# Controller_PCB_v1.net
KiCad netlist of a schematic drawn in EAGLE
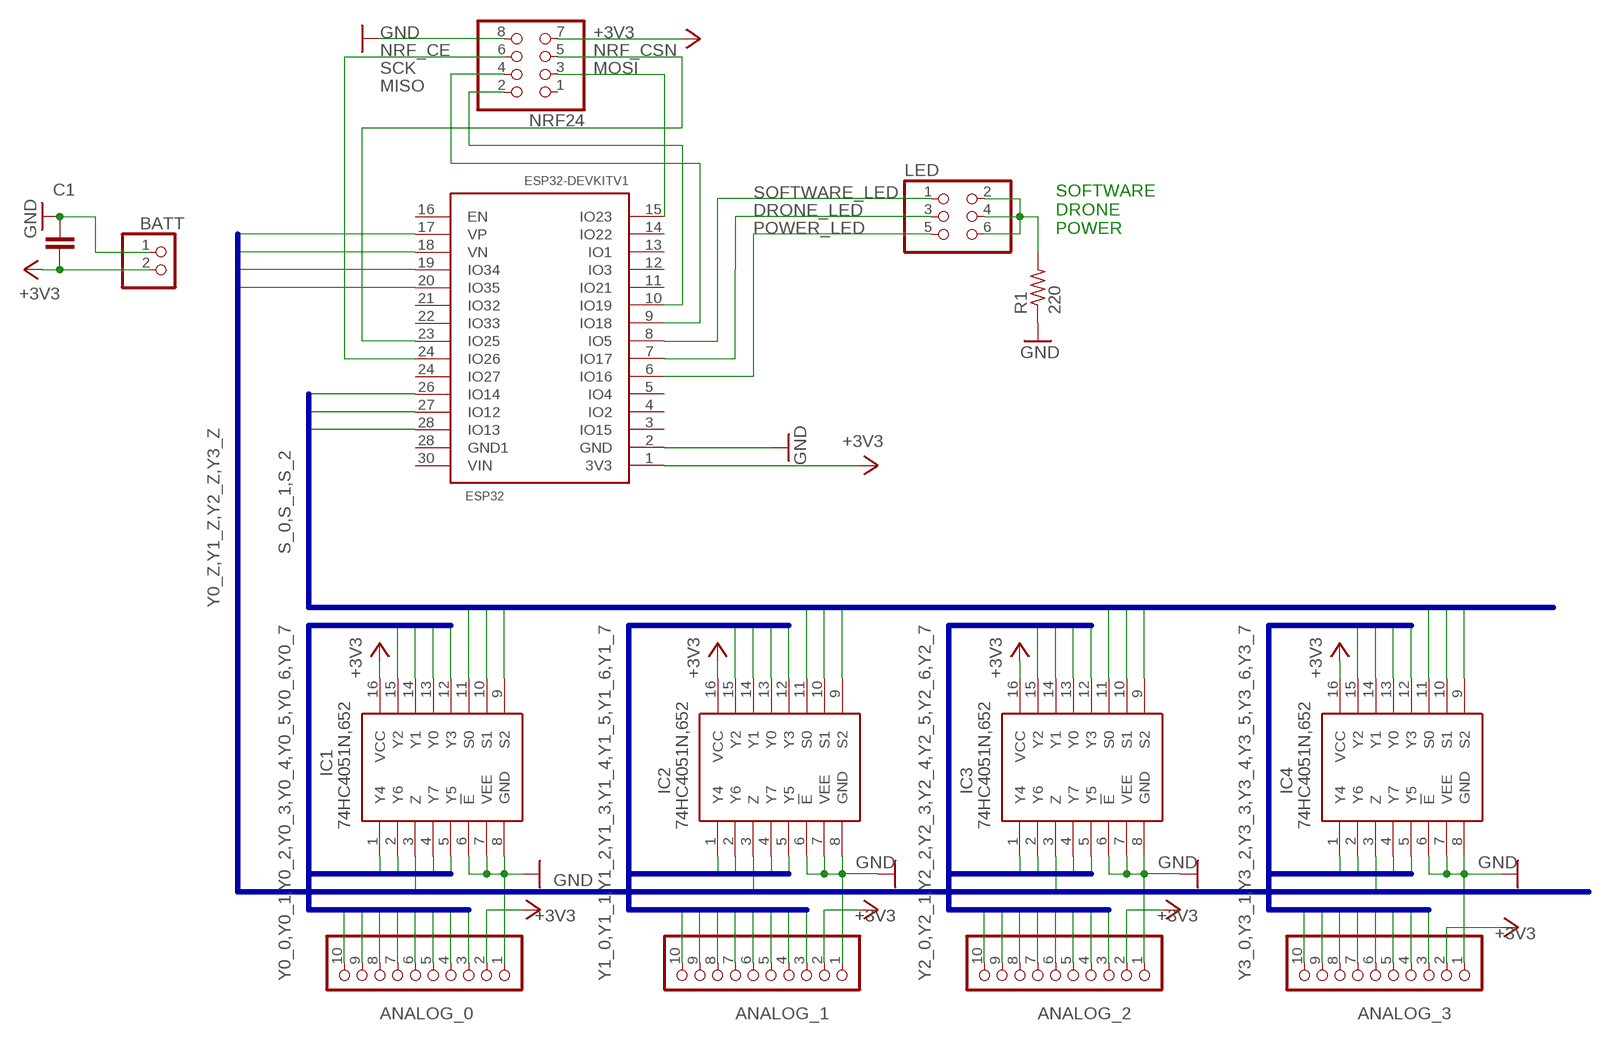
[diagram p0: schematic, sheet 1]

(export (version "E")
  (design (tool "Eeschema 10.0.6"))
  (components
    (comp (ref "ANALOG_0")
      (value "PINHD-1X10/90")
      (footprint "eagle-import:1X10_90")
      (libsource (lib "eagle-import") (part "PINHD-1X10/90"))
    )
    (comp (ref "ANALOG_1")
      (value "PINHD-1X10/90")
      (footprint "eagle-import:1X10_90")
      (libsource (lib "eagle-import") (part "PINHD-1X10/90"))
    )
    (comp (ref "ANALOG_2")
      (value "PINHD-1X10/90")
      (footprint "eagle-import:1X10_90")
      (libsource (lib "eagle-import") (part "PINHD-1X10/90"))
    )
    (comp (ref "ANALOG_3")
      (value "PINHD-1X10/90")
      (footprint "eagle-import:1X10_90")
      (libsource (lib "eagle-import") (part "PINHD-1X10/90"))
    )
    (comp (ref "BATT")
      (value "PINHD-1X2")
      (footprint "eagle-import:1X02")
      (libsource (lib "eagle-import") (part "PINHD-1X2"))
    )
    (comp (ref "C1")
      (value "C2.5/2")
      (footprint "eagle-import:C2.5-2")
      (libsource (lib "eagle-import") (part "C2.5/2"))
    )
    (comp (ref "ESP32")
      (value "ESP32DEVKITV1")
      (footprint "eagle-import:ESP32-DEVKITV1")
      (libsource (lib "eagle-import") (part "ESP32DEVKITV1"))
    )
    (comp (ref "IC1")
      (value "74HC4051N,652")
      (footprint "eagle-import:DIP802W53P254L1902H420Q16N")
      (libsource (lib "eagle-import") (part "74HC4051N,652"))
    )
    (comp (ref "IC2")
      (value "74HC4051N,652")
      (footprint "eagle-import:DIP802W53P254L1902H420Q16N")
      (libsource (lib "eagle-import") (part "74HC4051N,652"))
    )
    (comp (ref "IC3")
      (value "74HC4051N,652")
      (footprint "eagle-import:DIP802W53P254L1902H420Q16N")
      (libsource (lib "eagle-import") (part "74HC4051N,652"))
    )
    (comp (ref "IC4")
      (value "74HC4051N,652")
      (footprint "eagle-import:DIP802W53P254L1902H420Q16N")
      (libsource (lib "eagle-import") (part "74HC4051N,652"))
    )
    (comp (ref "LED")
      (value "PINHD-2X3")
      (footprint "eagle-import:2X03")
      (libsource (lib "eagle-import") (part "PINHD-2X3"))
    )
    (comp (ref "NRF24")
      (value "PINHD-2X4/90")
      (footprint "eagle-import:2X04_90")
      (libsource (lib "eagle-import") (part "PINHD-2X4/90"))
    )
    (comp (ref "R1")
      (value "220")
      (footprint "eagle-import:0204_7")
      (libsource (lib "eagle-import") (part "R-US_0204/7"))
    )
  )
  (nets
    (net (code "1") (name "+3V3") (class "Default")
      (node (ref "ANALOG_0") (pin "2") (pinfunction "2_2") (pintype "passive"))
      (node (ref "ANALOG_1") (pin "2") (pinfunction "2_2") (pintype "passive"))
      (node (ref "ANALOG_2") (pin "2") (pinfunction "2_2") (pintype "passive"))
      (node (ref "ANALOG_3") (pin "2") (pinfunction "2_2") (pintype "passive"))
      (node (ref "BATT") (pin "2") (pinfunction "2_2") (pintype "passive"))
      (node (ref "C1") (pin "2") (pinfunction "2_2") (pintype "passive"))
      (node (ref "ESP32") (pin "1") (pinfunction "3V3_1") (pintype "bidirectional"))
      (node (ref "IC1") (pin "16") (pinfunction "VCC_16") (pintype "bidirectional"))
      (node (ref "IC2") (pin "16") (pinfunction "VCC_16") (pintype "bidirectional"))
      (node (ref "IC3") (pin "16") (pinfunction "VCC_16") (pintype "bidirectional"))
      (node (ref "IC4") (pin "16") (pinfunction "VCC_16") (pintype "bidirectional"))
      (node (ref "NRF24") (pin "7") (pinfunction "7_7") (pintype "passive"))
    )
    (net (code "2") (name "/DRONE_LED") (class "Default")
      (node (ref "ESP32") (pin "7") (pinfunction "IO17_7") (pintype "bidirectional"))
      (node (ref "LED") (pin "3") (pinfunction "3_3") (pintype "passive"))
    )
    (net (code "3") (name "/MISO") (class "Default")
      (node (ref "ESP32") (pin "10") (pinfunction "IO19_10") (pintype "bidirectional"))
      (node (ref "NRF24") (pin "2") (pinfunction "2_2") (pintype "passive"))
    )
    (net (code "4") (name "/MOSI") (class "Default")
      (node (ref "ESP32") (pin "15") (pinfunction "IO23_15") (pintype "bidirectional"))
      (node (ref "NRF24") (pin "3") (pinfunction "3_3") (pintype "passive"))
    )
    (net (code "5") (name "/NRF_CE") (class "Default")
      (node (ref "ESP32") (pin "24") (pinfunction "IO26_24") (pintype "bidirectional"))
      (node (ref "NRF24") (pin "6") (pinfunction "6_6") (pintype "passive"))
    )
    (net (code "6") (name "/NRF_CSN") (class "Default")
      (node (ref "ESP32") (pin "23") (pinfunction "IO25_23") (pintype "bidirectional"))
      (node (ref "NRF24") (pin "5") (pinfunction "5_5") (pintype "passive"))
    )
    (net (code "7") (name "/POWER_LED") (class "Default")
      (node (ref "ESP32") (pin "6") (pinfunction "IO16_6") (pintype "bidirectional"))
      (node (ref "LED") (pin "5") (pinfunction "5_5") (pintype "passive"))
    )
    (net (code "8") (name "/SCK") (class "Default")
      (node (ref "ESP32") (pin "9") (pinfunction "IO18_9") (pintype "bidirectional"))
      (node (ref "NRF24") (pin "4") (pinfunction "4_4") (pintype "passive"))
    )
    (net (code "9") (name "/SOFTWARE_LED") (class "Default")
      (node (ref "ESP32") (pin "8") (pinfunction "IO5_8") (pintype "bidirectional"))
      (node (ref "LED") (pin "1") (pinfunction "1_1") (pintype "passive"))
    )
    (net (code "10") (name "/S_0") (class "Default")
      (node (ref "ESP32") (pin "28") (pinfunction "IO13_28") (pintype "bidirectional"))
      (node (ref "IC1") (pin "11") (pinfunction "S0_11") (pintype "bidirectional"))
      (node (ref "IC2") (pin "11") (pinfunction "S0_11") (pintype "bidirectional"))
      (node (ref "IC3") (pin "11") (pinfunction "S0_11") (pintype "bidirectional"))
      (node (ref "IC4") (pin "11") (pinfunction "S0_11") (pintype "bidirectional"))
    )
    (net (code "11") (name "/S_1") (class "Default")
      (node (ref "ESP32") (pin "27") (pinfunction "IO12_27") (pintype "bidirectional"))
      (node (ref "IC1") (pin "10") (pinfunction "S1_10") (pintype "bidirectional"))
      (node (ref "IC2") (pin "10") (pinfunction "S1_10") (pintype "bidirectional"))
      (node (ref "IC3") (pin "10") (pinfunction "S1_10") (pintype "bidirectional"))
      (node (ref "IC4") (pin "10") (pinfunction "S1_10") (pintype "bidirectional"))
    )
    (net (code "12") (name "/S_2") (class "Default")
      (node (ref "ESP32") (pin "26") (pinfunction "IO14_26") (pintype "bidirectional"))
      (node (ref "IC1") (pin "9") (pinfunction "S2_9") (pintype "bidirectional"))
      (node (ref "IC2") (pin "9") (pinfunction "S2_9") (pintype "bidirectional"))
      (node (ref "IC3") (pin "9") (pinfunction "S2_9") (pintype "bidirectional"))
      (node (ref "IC4") (pin "9") (pinfunction "S2_9") (pintype "bidirectional"))
    )
    (net (code "13") (name "/Y0_0") (class "Default")
      (node (ref "ANALOG_0") (pin "3") (pinfunction "3_3") (pintype "passive"))
      (node (ref "IC1") (pin "13") (pinfunction "Y0_13") (pintype "bidirectional"))
    )
    (net (code "14") (name "/Y0_1") (class "Default")
      (node (ref "ANALOG_0") (pin "4") (pinfunction "4_4") (pintype "passive"))
      (node (ref "IC1") (pin "14") (pinfunction "Y1_14") (pintype "bidirectional"))
    )
    (net (code "15") (name "/Y0_2") (class "Default")
      (node (ref "ANALOG_0") (pin "5") (pinfunction "5_5") (pintype "passive"))
      (node (ref "IC1") (pin "15") (pinfunction "Y2_15") (pintype "bidirectional"))
    )
    (net (code "16") (name "/Y0_3") (class "Default")
      (node (ref "ANALOG_0") (pin "6") (pinfunction "6_6") (pintype "passive"))
      (node (ref "IC1") (pin "12") (pinfunction "Y3_12") (pintype "bidirectional"))
    )
    (net (code "17") (name "/Y0_4") (class "Default")
      (node (ref "ANALOG_0") (pin "7") (pinfunction "7_7") (pintype "passive"))
      (node (ref "IC1") (pin "1") (pinfunction "Y4_1") (pintype "bidirectional"))
    )
    (net (code "18") (name "/Y0_5") (class "Default")
      (node (ref "ANALOG_0") (pin "8") (pinfunction "8_8") (pintype "passive"))
      (node (ref "IC1") (pin "5") (pinfunction "Y5_5") (pintype "bidirectional"))
    )
    (net (code "19") (name "/Y0_6") (class "Default")
      (node (ref "ANALOG_0") (pin "9") (pinfunction "9_9") (pintype "passive"))
      (node (ref "IC1") (pin "2") (pinfunction "Y6_2") (pintype "bidirectional"))
    )
    (net (code "20") (name "/Y0_7") (class "Default")
      (node (ref "ANALOG_0") (pin "10") (pinfunction "10_10") (pintype "passive"))
      (node (ref "IC1") (pin "4") (pinfunction "Y7_4") (pintype "bidirectional"))
    )
    (net (code "21") (name "/Y0_Z") (class "Default")
      (node (ref "ESP32") (pin "17") (pinfunction "VP_17") (pintype "bidirectional"))
      (node (ref "IC1") (pin "3") (pinfunction "Z_3") (pintype "bidirectional"))
    )
    (net (code "22") (name "/Y1_0") (class "Default")
      (node (ref "ANALOG_1") (pin "3") (pinfunction "3_3") (pintype "passive"))
      (node (ref "IC2") (pin "13") (pinfunction "Y0_13") (pintype "bidirectional"))
    )
    (net (code "23") (name "/Y1_1") (class "Default")
      (node (ref "ANALOG_1") (pin "4") (pinfunction "4_4") (pintype "passive"))
      (node (ref "IC2") (pin "14") (pinfunction "Y1_14") (pintype "bidirectional"))
    )
    (net (code "24") (name "/Y1_2") (class "Default")
      (node (ref "ANALOG_1") (pin "5") (pinfunction "5_5") (pintype "passive"))
      (node (ref "IC2") (pin "15") (pinfunction "Y2_15") (pintype "bidirectional"))
    )
    (net (code "25") (name "/Y1_3") (class "Default")
      (node (ref "ANALOG_1") (pin "6") (pinfunction "6_6") (pintype "passive"))
      (node (ref "IC2") (pin "12") (pinfunction "Y3_12") (pintype "bidirectional"))
    )
    (net (code "26") (name "/Y1_4") (class "Default")
      (node (ref "ANALOG_1") (pin "7") (pinfunction "7_7") (pintype "passive"))
      (node (ref "IC2") (pin "1") (pinfunction "Y4_1") (pintype "bidirectional"))
    )
    (net (code "27") (name "/Y1_5") (class "Default")
      (node (ref "ANALOG_1") (pin "8") (pinfunction "8_8") (pintype "passive"))
      (node (ref "IC2") (pin "5") (pinfunction "Y5_5") (pintype "bidirectional"))
    )
    (net (code "28") (name "/Y1_6") (class "Default")
      (node (ref "ANALOG_1") (pin "9") (pinfunction "9_9") (pintype "passive"))
      (node (ref "IC2") (pin "2") (pinfunction "Y6_2") (pintype "bidirectional"))
    )
    (net (code "29") (name "/Y1_7") (class "Default")
      (node (ref "ANALOG_1") (pin "10") (pinfunction "10_10") (pintype "passive"))
      (node (ref "IC2") (pin "4") (pinfunction "Y7_4") (pintype "bidirectional"))
    )
    (net (code "30") (name "/Y1_Z") (class "Default")
      (node (ref "ESP32") (pin "18") (pinfunction "VN_18") (pintype "bidirectional"))
      (node (ref "IC2") (pin "3") (pinfunction "Z_3") (pintype "bidirectional"))
    )
    (net (code "31") (name "/Y2_0") (class "Default")
      (node (ref "ANALOG_2") (pin "3") (pinfunction "3_3") (pintype "passive"))
      (node (ref "IC3") (pin "13") (pinfunction "Y0_13") (pintype "bidirectional"))
    )
    (net (code "32") (name "/Y2_1") (class "Default")
      (node (ref "ANALOG_2") (pin "4") (pinfunction "4_4") (pintype "passive"))
      (node (ref "IC3") (pin "14") (pinfunction "Y1_14") (pintype "bidirectional"))
    )
    (net (code "33") (name "/Y2_2") (class "Default")
      (node (ref "ANALOG_2") (pin "5") (pinfunction "5_5") (pintype "passive"))
      (node (ref "IC3") (pin "15") (pinfunction "Y2_15") (pintype "bidirectional"))
    )
    (net (code "34") (name "/Y2_3") (class "Default")
      (node (ref "ANALOG_2") (pin "6") (pinfunction "6_6") (pintype "passive"))
      (node (ref "IC3") (pin "12") (pinfunction "Y3_12") (pintype "bidirectional"))
    )
    (net (code "35") (name "/Y2_4") (class "Default")
      (node (ref "ANALOG_2") (pin "7") (pinfunction "7_7") (pintype "passive"))
      (node (ref "IC3") (pin "1") (pinfunction "Y4_1") (pintype "bidirectional"))
    )
    (net (code "36") (name "/Y2_5") (class "Default")
      (node (ref "ANALOG_2") (pin "8") (pinfunction "8_8") (pintype "passive"))
      (node (ref "IC3") (pin "5") (pinfunction "Y5_5") (pintype "bidirectional"))
    )
    (net (code "37") (name "/Y2_6") (class "Default")
      (node (ref "ANALOG_2") (pin "9") (pinfunction "9_9") (pintype "passive"))
      (node (ref "IC3") (pin "2") (pinfunction "Y6_2") (pintype "bidirectional"))
    )
    (net (code "38") (name "/Y2_7") (class "Default")
      (node (ref "ANALOG_2") (pin "10") (pinfunction "10_10") (pintype "passive"))
      (node (ref "IC3") (pin "4") (pinfunction "Y7_4") (pintype "bidirectional"))
    )
    (net (code "39") (name "/Y2_Z") (class "Default")
      (node (ref "ESP32") (pin "19") (pinfunction "IO34_19") (pintype "bidirectional"))
      (node (ref "IC3") (pin "3") (pinfunction "Z_3") (pintype "bidirectional"))
    )
    (net (code "40") (name "/Y3_0") (class "Default")
      (node (ref "ANALOG_3") (pin "3") (pinfunction "3_3") (pintype "passive"))
      (node (ref "IC4") (pin "13") (pinfunction "Y0_13") (pintype "bidirectional"))
    )
    (net (code "41") (name "/Y3_1") (class "Default")
      (node (ref "ANALOG_3") (pin "4") (pinfunction "4_4") (pintype "passive"))
      (node (ref "IC4") (pin "14") (pinfunction "Y1_14") (pintype "bidirectional"))
    )
    (net (code "42") (name "/Y3_2") (class "Default")
      (node (ref "ANALOG_3") (pin "5") (pinfunction "5_5") (pintype "passive"))
      (node (ref "IC4") (pin "15") (pinfunction "Y2_15") (pintype "bidirectional"))
    )
    (net (code "43") (name "/Y3_3") (class "Default")
      (node (ref "ANALOG_3") (pin "6") (pinfunction "6_6") (pintype "passive"))
      (node (ref "IC4") (pin "12") (pinfunction "Y3_12") (pintype "bidirectional"))
    )
    (net (code "44") (name "/Y3_4") (class "Default")
      (node (ref "ANALOG_3") (pin "7") (pinfunction "7_7") (pintype "passive"))
      (node (ref "IC4") (pin "1") (pinfunction "Y4_1") (pintype "bidirectional"))
    )
    (net (code "45") (name "/Y3_5") (class "Default")
      (node (ref "ANALOG_3") (pin "8") (pinfunction "8_8") (pintype "passive"))
      (node (ref "IC4") (pin "5") (pinfunction "Y5_5") (pintype "bidirectional"))
    )
    (net (code "46") (name "/Y3_6") (class "Default")
      (node (ref "ANALOG_3") (pin "9") (pinfunction "9_9") (pintype "passive"))
      (node (ref "IC4") (pin "2") (pinfunction "Y6_2") (pintype "bidirectional"))
    )
    (net (code "47") (name "/Y3_7") (class "Default")
      (node (ref "ANALOG_3") (pin "10") (pinfunction "10_10") (pintype "passive"))
      (node (ref "IC4") (pin "4") (pinfunction "Y7_4") (pintype "bidirectional"))
    )
    (net (code "48") (name "/Y3_Z") (class "Default")
      (node (ref "ESP32") (pin "20") (pinfunction "IO35_20") (pintype "bidirectional"))
      (node (ref "IC4") (pin "3") (pinfunction "Z_3") (pintype "bidirectional"))
    )
    (net (code "51") (name "GND") (class "Default")
      (node (ref "ANALOG_0") (pin "1") (pinfunction "1_1") (pintype "passive"))
      (node (ref "ANALOG_1") (pin "1") (pinfunction "1_1") (pintype "passive"))
      (node (ref "ANALOG_2") (pin "1") (pinfunction "1_1") (pintype "passive"))
      (node (ref "ANALOG_3") (pin "1") (pinfunction "1_1") (pintype "passive"))
      (node (ref "BATT") (pin "1") (pinfunction "1_1") (pintype "passive"))
      (node (ref "C1") (pin "1") (pinfunction "1_1") (pintype "passive"))
      (node (ref "ESP32") (pin "2") (pinfunction "GND_2") (pintype "bidirectional"))
      (node (ref "IC1") (pin "6") (pinfunction "~{E}_6") (pintype "bidirectional"))
      (node (ref "IC1") (pin "7") (pinfunction "VEE_7") (pintype "bidirectional"))
      (node (ref "IC1") (pin "8") (pinfunction "GND_8") (pintype "bidirectional"))
      (node (ref "IC2") (pin "6") (pinfunction "~{E}_6") (pintype "bidirectional"))
      (node (ref "IC2") (pin "7") (pinfunction "VEE_7") (pintype "bidirectional"))
      (node (ref "IC2") (pin "8") (pinfunction "GND_8") (pintype "bidirectional"))
      (node (ref "IC3") (pin "6") (pinfunction "~{E}_6") (pintype "bidirectional"))
      (node (ref "IC3") (pin "7") (pinfunction "VEE_7") (pintype "bidirectional"))
      (node (ref "IC3") (pin "8") (pinfunction "GND_8") (pintype "bidirectional"))
      (node (ref "IC4") (pin "6") (pinfunction "~{E}_6") (pintype "bidirectional"))
      (node (ref "IC4") (pin "7") (pinfunction "VEE_7") (pintype "bidirectional"))
      (node (ref "IC4") (pin "8") (pinfunction "GND_8") (pintype "bidirectional"))
      (node (ref "NRF24") (pin "8") (pinfunction "8_8") (pintype "passive"))
      (node (ref "R1") (pin "1") (pinfunction "1_1") (pintype "passive"))
    )
    (net (code "52") (name "Net-(LED-Pad2)") (class "Default")
      (node (ref "LED") (pin "2") (pinfunction "2_2") (pintype "passive"))
      (node (ref "LED") (pin "4") (pinfunction "4_4") (pintype "passive"))
      (node (ref "LED") (pin "6") (pinfunction "6_6") (pintype "passive"))
      (node (ref "R1") (pin "2") (pinfunction "2_2") (pintype "passive"))
    )
    (net (code "53") (name "unconnected-(ESP32-EN-Pad16)") (class "Default")
      (node (ref "ESP32") (pin "16") (pinfunction "EN_16") (pintype "bidirectional"))
    )
    (net (code "54") (name "unconnected-(ESP32-GND1-Pad28)") (class "Default")
      (node (ref "ESP32") (pin "28") (pinfunction "GND1_28") (pintype "bidirectional"))
    )
    (net (code "55") (name "unconnected-(ESP32-IO1-Pad13)") (class "Default")
      (node (ref "ESP32") (pin "13") (pinfunction "IO1_13") (pintype "bidirectional"))
    )
    (net (code "56") (name "unconnected-(ESP32-IO2-Pad4)") (class "Default")
      (node (ref "ESP32") (pin "4") (pinfunction "IO2_4") (pintype "bidirectional"))
    )
    (net (code "57") (name "unconnected-(ESP32-IO3-Pad12)") (class "Default")
      (node (ref "ESP32") (pin "12") (pinfunction "IO3_12") (pintype "bidirectional"))
    )
    (net (code "58") (name "unconnected-(ESP32-IO4-Pad5)") (class "Default")
      (node (ref "ESP32") (pin "5") (pinfunction "IO4_5") (pintype "bidirectional"))
    )
    (net (code "59") (name "unconnected-(ESP32-IO15-Pad3)") (class "Default")
      (node (ref "ESP32") (pin "3") (pinfunction "IO15_3") (pintype "bidirectional"))
    )
    (net (code "60") (name "unconnected-(ESP32-IO21-Pad11)") (class "Default")
      (node (ref "ESP32") (pin "11") (pinfunction "IO21_11") (pintype "bidirectional"))
    )
    (net (code "61") (name "unconnected-(ESP32-IO22-Pad14)") (class "Default")
      (node (ref "ESP32") (pin "14") (pinfunction "IO22_14") (pintype "bidirectional"))
    )
    (net (code "62") (name "unconnected-(ESP32-IO27-Pad24)") (class "Default")
      (node (ref "ESP32") (pin "24") (pinfunction "IO27_24") (pintype "bidirectional"))
    )
    (net (code "63") (name "unconnected-(ESP32-IO32-Pad21)") (class "Default")
      (node (ref "ESP32") (pin "21") (pinfunction "IO32_21") (pintype "bidirectional"))
    )
    (net (code "64") (name "unconnected-(ESP32-IO33-Pad22)") (class "Default")
      (node (ref "ESP32") (pin "22") (pinfunction "IO33_22") (pintype "bidirectional"))
    )
    (net (code "65") (name "unconnected-(ESP32-VIN-Pad30)") (class "Default")
      (node (ref "ESP32") (pin "30") (pinfunction "VIN_30") (pintype "bidirectional"))
    )
    (net (code "66") (name "unconnected-(NRF24-Pad1)") (class "Default")
      (node (ref "NRF24") (pin "1") (pinfunction "1_1") (pintype "passive"))
    )
  )
)
